# RPi_Clock_I2C.net
KiCad netlist of a schematic drawn in EAGLE
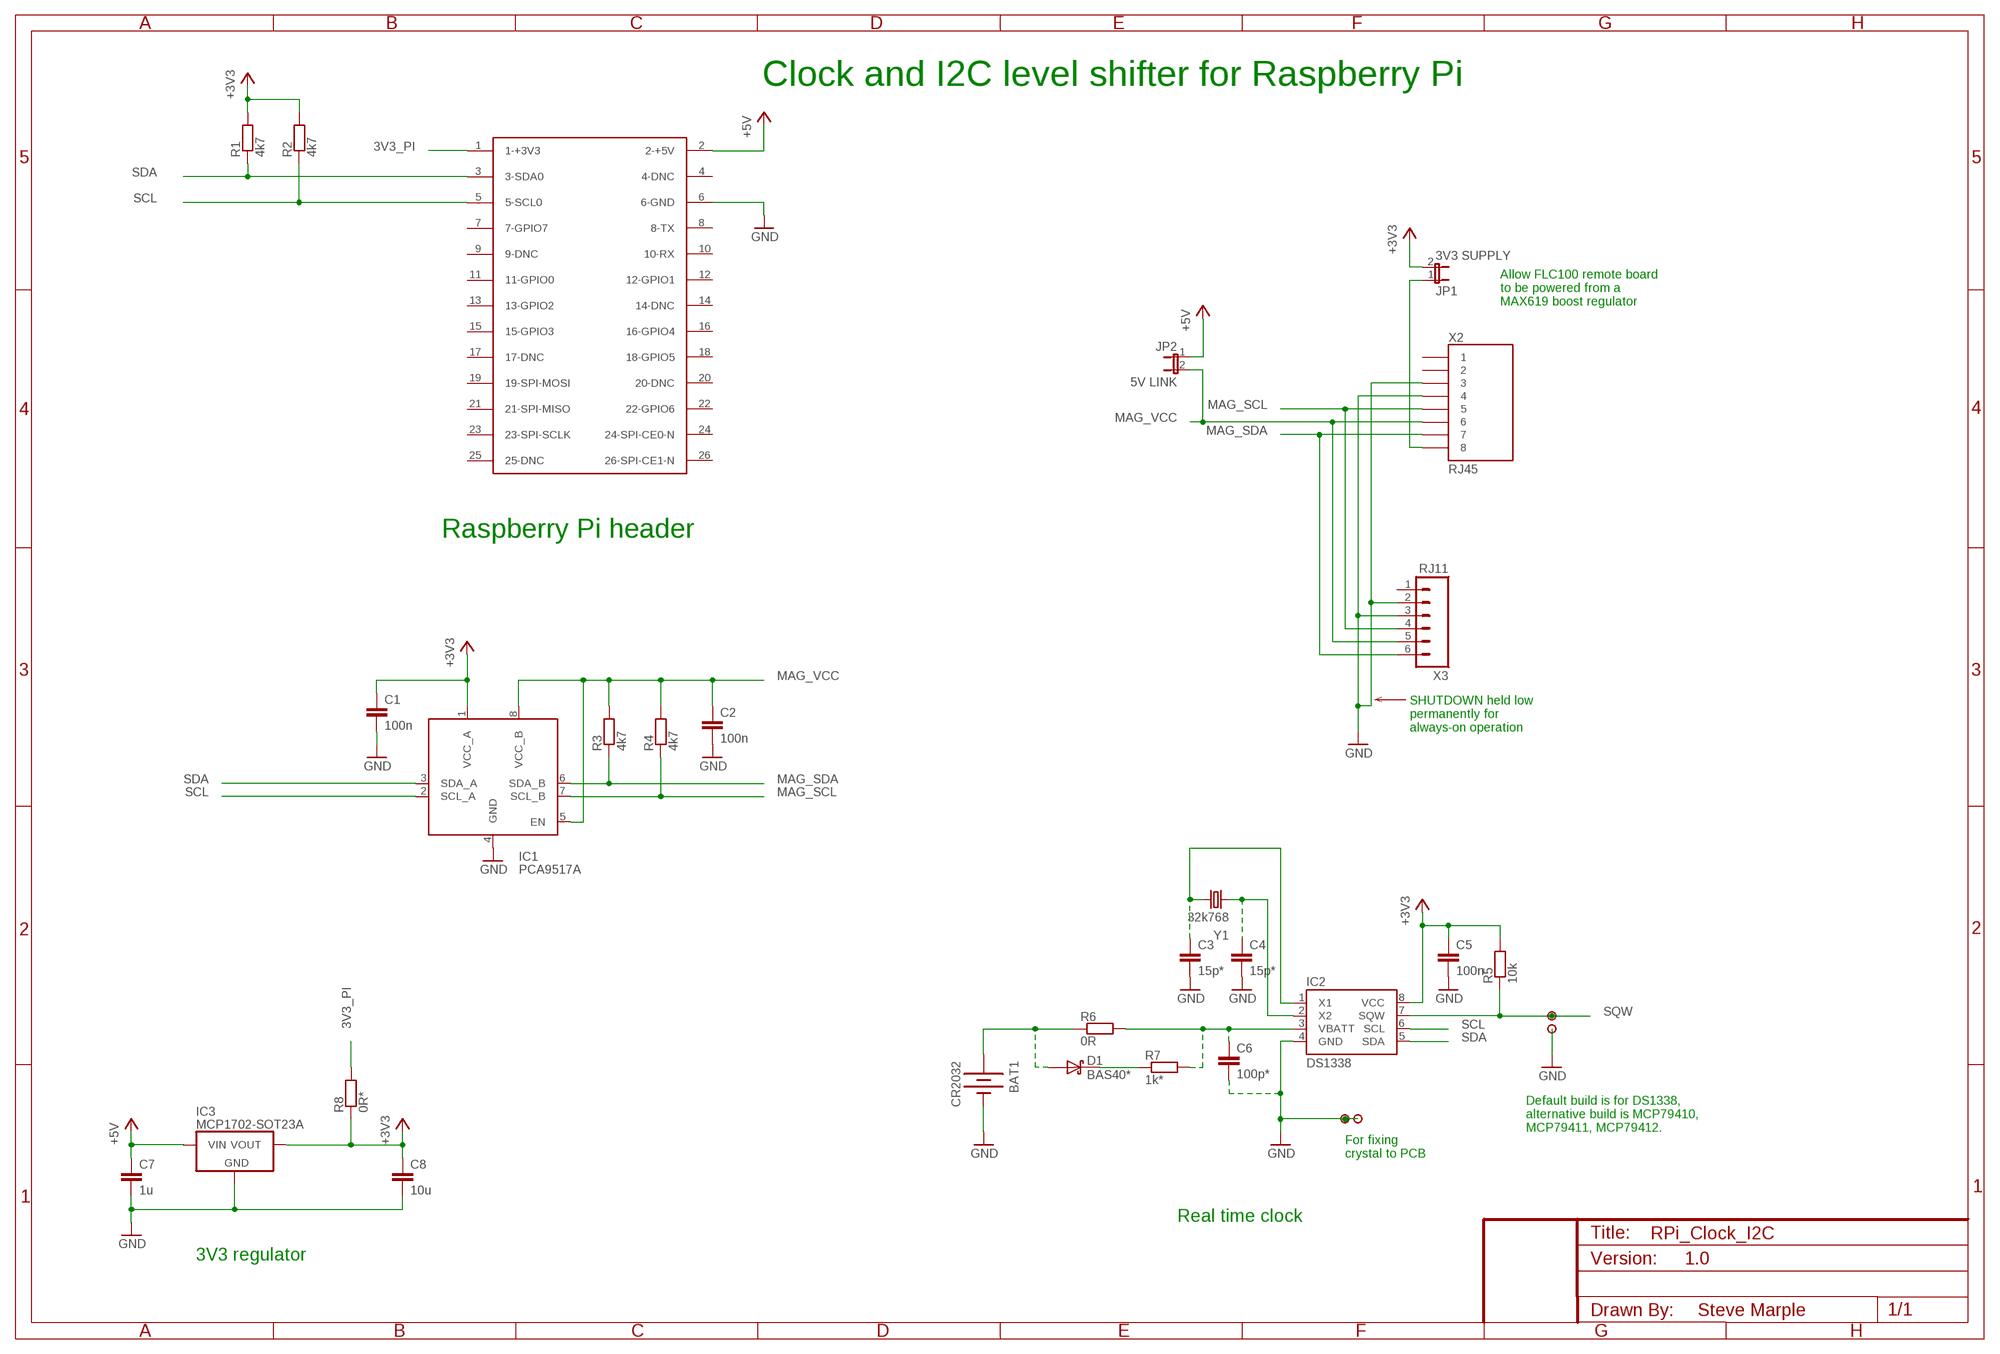
[diagram p0: schematic, sheet 1]

(export (version "E")
  (design (tool "Eeschema 10.0.6"))
  (components
    (comp (ref "BAT1")
      (value "CR2032")
      (footprint "eagle-import:BATTCOM_20MM_PTH")
      (libsource (lib "eagle-import") (part "BATTERY20PTH"))
    )
    (comp (ref "C1")
      (value "100n")
      (footprint "eagle-import:1206-HAND")
      (libsource (lib "eagle-import") (part "C-EU1206-HAND"))
    )
    (comp (ref "C2")
      (value "100n")
      (footprint "eagle-import:1206-HAND")
      (libsource (lib "eagle-import") (part "C-EU1206-HAND"))
    )
    (comp (ref "C3")
      (value "15p*")
      (footprint "eagle-import:0805-HAND")
      (libsource (lib "eagle-import") (part "C-EU0805-HAND"))
    )
    (comp (ref "C4")
      (value "15p*")
      (footprint "eagle-import:0805-HAND")
      (libsource (lib "eagle-import") (part "C-EU0805-HAND"))
    )
    (comp (ref "C5")
      (value "100n")
      (footprint "eagle-import:1206-HAND")
      (libsource (lib "eagle-import") (part "C-EU1206-HAND"))
    )
    (comp (ref "C6")
      (value "100p*")
      (footprint "eagle-import:1206-HAND")
      (libsource (lib "eagle-import") (part "C-EU1206-HAND"))
    )
    (comp (ref "C7")
      (value "1u")
      (footprint "eagle-import:1206-HAND")
      (libsource (lib "eagle-import") (part "C-EU1206-HAND"))
    )
    (comp (ref "C8")
      (value "10u")
      (footprint "eagle-import:1206-HAND")
      (libsource (lib "eagle-import") (part "C-EU1206-HAND"))
    )
    (comp (ref "D1")
      (value "BAS40*")
      (footprint "eagle-import:SOT23-3-HAND")
      (libsource (lib "eagle-import") (part "DIODE-SCHOTTKYSOT23-1-3-HAND"))
    )
    (comp (ref "IC1")
      (value "PCA9517A")
      (footprint "eagle-import:SO08")
      (libsource (lib "eagle-import") (part "PCA9517ASOIC"))
    )
    (comp (ref "IC2")
      (value "DS1338")
      (footprint "eagle-import:SO08")
      (libsource (lib "eagle-import") (part "DS1307SO08"))
    )
    (comp (ref "IC3")
      (value "MCP1702-SOT23A")
      (footprint "eagle-import:SOT23-3-HAND")
      (libsource (lib "eagle-import") (part "MCP1702SOT23-HAND"))
    )
    (comp (ref "JP1")
      (value "3V3 SUPPLY")
      (footprint "eagle-import:1X02")
      (libsource (lib "eagle-import") (part "JUMPER-2PTH"))
    )
    (comp (ref "JP2")
      (value "5V LINK")
      (footprint "eagle-import:1X02")
      (libsource (lib "eagle-import") (part "JUMPER-2PTH"))
    )
    (comp (ref "R1")
      (value "4k7")
      (footprint "eagle-import:1206-HAND")
      (libsource (lib "eagle-import") (part "RESISTOR1206-HAND"))
    )
    (comp (ref "R2")
      (value "4k7")
      (footprint "eagle-import:1206-HAND")
      (libsource (lib "eagle-import") (part "RESISTOR1206-HAND"))
    )
    (comp (ref "R3")
      (value "4k7")
      (footprint "eagle-import:1206-HAND")
      (libsource (lib "eagle-import") (part "RESISTOR1206-HAND"))
    )
    (comp (ref "R4")
      (value "4k7")
      (footprint "eagle-import:1206-HAND")
      (libsource (lib "eagle-import") (part "RESISTOR1206-HAND"))
    )
    (comp (ref "R5")
      (value "10k")
      (footprint "eagle-import:1206-HAND")
      (libsource (lib "eagle-import") (part "RESISTOR1206-HAND"))
    )
    (comp (ref "R6")
      (value "0R")
      (footprint "eagle-import:1206-HAND")
      (libsource (lib "eagle-import") (part "RESISTOR1206-HAND"))
    )
    (comp (ref "R7")
      (value "1k*")
      (footprint "eagle-import:1206-HAND")
      (libsource (lib "eagle-import") (part "RESISTOR1206-HAND"))
    )
    (comp (ref "R8")
      (value "0R*")
      (footprint "eagle-import:1206-HAND")
      (libsource (lib "eagle-import") (part "RESISTOR1206-HAND"))
    )
    (comp (ref "U$1")
      (value "PAD")
      (footprint "eagle-import:PAD")
      (libsource (lib "eagle-import") (part "PAD"))
    )
    (comp (ref "U$2")
      (value "PAD")
      (footprint "eagle-import:PAD")
      (libsource (lib "eagle-import") (part "PAD"))
    )
    (comp (ref "U$3")
      (value "PADSMALL")
      (footprint "eagle-import:PAD-SMALL")
      (libsource (lib "eagle-import") (part "PADSMALL"))
    )
    (comp (ref "U$4")
      (value "PADSMALL")
      (footprint "eagle-import:PAD-SMALL")
      (libsource (lib "eagle-import") (part "PADSMALL"))
    )
    (comp (ref "X1")
      (value "P1")
      (footprint "eagle-import:RASPBERRY-PI-HEADER")
      (libsource (lib "eagle-import") (part "RASPBERRY-PIHEADER"))
    )
    (comp (ref "X2")
      (value "RJ45")
      (footprint "eagle-import:RJ45-8")
      (libsource (lib "eagle-import") (part "RJ45-8PTH"))
    )
    (comp (ref "X3")
      (value "RJ11")
      (footprint "eagle-import:RJ11-6")
      (libsource (lib "eagle-import") (part "RJ11-6PTH"))
    )
    (comp (ref "Y1")
      (value "32k768")
      (footprint "eagle-import:TC38H")
      (libsource (lib "eagle-import") (part "CRYSTALTC38H"))
    )
  )
  (nets
    (net (code "1") (name "+3V3") (class "Default")
      (node (ref "C1") (pin "1") (pinfunction "1_1") (pintype "passive"))
      (node (ref "C5") (pin "1") (pinfunction "1_1") (pintype "passive"))
      (node (ref "C8") (pin "1") (pinfunction "1_1") (pintype "passive"))
      (node (ref "IC1") (pin "1") (pinfunction "VCC_A_1") (pintype "power_in"))
      (node (ref "IC2") (pin "8") (pinfunction "VCC_8") (pintype "bidirectional"))
      (node (ref "IC3") (pin "2") (pinfunction "VOUT_2") (pintype "passive"))
      (node (ref "JP1") (pin "2") (pinfunction "2_2") (pintype "passive"))
      (node (ref "R1") (pin "2") (pinfunction "2_2") (pintype "passive"))
      (node (ref "R2") (pin "2") (pinfunction "2_2") (pintype "passive"))
      (node (ref "R5") (pin "2") (pinfunction "2_2") (pintype "passive"))
      (node (ref "R8") (pin "1") (pinfunction "1_1") (pintype "passive"))
    )
    (net (code "2") (name "+5V") (class "Default")
      (node (ref "C7") (pin "1") (pinfunction "1_1") (pintype "passive"))
      (node (ref "IC3") (pin "3") (pinfunction "VIN_3") (pintype "input"))
      (node (ref "JP2") (pin "1") (pinfunction "1_1") (pintype "passive"))
      (node (ref "X1") (pin "2") (pinfunction "2-+5V_2") (pintype "bidirectional"))
    )
    (net (code "3") (name "/3V3_PI") (class "Default")
      (node (ref "R8") (pin "2") (pinfunction "2_2") (pintype "passive"))
      (node (ref "X1") (pin "1") (pinfunction "1-+3V3_1") (pintype "bidirectional"))
    )
    (net (code "4") (name "/MAG_SCL") (class "Default")
      (node (ref "IC1") (pin "7") (pinfunction "SCL_B_7") (pintype "bidirectional"))
      (node (ref "R4") (pin "1") (pinfunction "1_1") (pintype "passive"))
      (node (ref "X2") (pin "5") (pinfunction "5_5") (pintype "bidirectional"))
      (node (ref "X3") (pin "4") (pinfunction "4_4") (pintype "passive"))
    )
    (net (code "5") (name "/MAG_SDA") (class "Default")
      (node (ref "IC1") (pin "6") (pinfunction "SDA_B_6") (pintype "bidirectional"))
      (node (ref "R3") (pin "1") (pinfunction "1_1") (pintype "passive"))
      (node (ref "X2") (pin "7") (pinfunction "7_7") (pintype "bidirectional"))
      (node (ref "X3") (pin "6") (pinfunction "6_6") (pintype "passive"))
    )
    (net (code "6") (name "/MAG_VCC") (class "Default")
      (node (ref "C2") (pin "1") (pinfunction "1_1") (pintype "passive"))
      (node (ref "IC1") (pin "5") (pinfunction "EN_5") (pintype "bidirectional"))
      (node (ref "IC1") (pin "8") (pinfunction "VCC_B_8") (pintype "power_in"))
      (node (ref "JP2") (pin "2") (pinfunction "2_2") (pintype "passive"))
      (node (ref "R3") (pin "2") (pinfunction "2_2") (pintype "passive"))
      (node (ref "R4") (pin "2") (pinfunction "2_2") (pintype "passive"))
      (node (ref "X2") (pin "6") (pinfunction "6_6") (pintype "bidirectional"))
      (node (ref "X3") (pin "5") (pinfunction "5_5") (pintype "passive"))
    )
    (net (code "7") (name "/SCL") (class "Default")
      (node (ref "IC1") (pin "2") (pinfunction "SCL_A_2") (pintype "bidirectional"))
      (node (ref "IC2") (pin "6") (pinfunction "SCL_6") (pintype "bidirectional"))
      (node (ref "R2") (pin "1") (pinfunction "1_1") (pintype "passive"))
      (node (ref "X1") (pin "5") (pinfunction "5-SCL0_5") (pintype "bidirectional"))
    )
    (net (code "8") (name "/SDA") (class "Default")
      (node (ref "IC1") (pin "3") (pinfunction "SDA_A_3") (pintype "bidirectional"))
      (node (ref "IC2") (pin "5") (pinfunction "SDA_5") (pintype "bidirectional"))
      (node (ref "R1") (pin "1") (pinfunction "1_1") (pintype "passive"))
      (node (ref "X1") (pin "3") (pinfunction "3-SDA0_3") (pintype "bidirectional"))
    )
    (net (code "9") (name "/SQW") (class "Default")
      (node (ref "IC2") (pin "7") (pinfunction "SQW_7") (pintype "bidirectional"))
      (node (ref "R5") (pin "1") (pinfunction "1_1") (pintype "passive"))
      (node (ref "U$1") (pin "1") (pinfunction "1_1") (pintype "bidirectional"))
    )
    (net (code "10") (name "GND") (class "Default")
      (node (ref "BAT1") (pin "2") (pinfunction "-_2") (pintype "power_in"))
      (node (ref "C1") (pin "2") (pinfunction "2_2") (pintype "passive"))
      (node (ref "C2") (pin "2") (pinfunction "2_2") (pintype "passive"))
      (node (ref "C3") (pin "2") (pinfunction "2_2") (pintype "passive"))
      (node (ref "C4") (pin "2") (pinfunction "2_2") (pintype "passive"))
      (node (ref "C5") (pin "2") (pinfunction "2_2") (pintype "passive"))
      (node (ref "C6") (pin "2") (pinfunction "2_2") (pintype "passive"))
      (node (ref "C7") (pin "2") (pinfunction "2_2") (pintype "passive"))
      (node (ref "C8") (pin "2") (pinfunction "2_2") (pintype "passive"))
      (node (ref "IC1") (pin "4") (pinfunction "GND_4") (pintype "power_in"))
      (node (ref "IC2") (pin "4") (pinfunction "GND_4") (pintype "bidirectional"))
      (node (ref "IC3") (pin "1") (pinfunction "GND_1") (pintype "passive"))
      (node (ref "U$2") (pin "1") (pinfunction "1_1") (pintype "bidirectional"))
      (node (ref "U$3") (pin "1") (pinfunction "1_1") (pintype "bidirectional"))
      (node (ref "U$4") (pin "1") (pinfunction "1_1") (pintype "bidirectional"))
      (node (ref "X1") (pin "6") (pinfunction "6-GND_6") (pintype "bidirectional"))
      (node (ref "X2") (pin "3") (pinfunction "3_3") (pintype "bidirectional"))
      (node (ref "X2") (pin "4") (pinfunction "4_4") (pintype "bidirectional"))
      (node (ref "X3") (pin "2") (pinfunction "2_2") (pintype "passive"))
      (node (ref "X3") (pin "3") (pinfunction "3_3") (pintype "passive"))
    )
    (net (code "11") (name "Net-(BAT1-+)") (class "Default")
      (node (ref "BAT1") (pin "1") (pinfunction "+_1") (pintype "power_in"))
      (node (ref "D1") (pin "1") (pinfunction "A_1") (pintype "passive"))
      (node (ref "R6") (pin "1") (pinfunction "1_1") (pintype "passive"))
    )
    (net (code "12") (name "Net-(D1-C)") (class "Default")
      (node (ref "D1") (pin "3") (pinfunction "C_3") (pintype "passive"))
      (node (ref "R7") (pin "1") (pinfunction "1_1") (pintype "passive"))
    )
    (net (code "13") (name "Net-(IC2-VBATT)") (class "Default")
      (node (ref "C6") (pin "1") (pinfunction "1_1") (pintype "passive"))
      (node (ref "IC2") (pin "3") (pinfunction "VBATT_3") (pintype "bidirectional"))
      (node (ref "R6") (pin "2") (pinfunction "2_2") (pintype "passive"))
      (node (ref "R7") (pin "2") (pinfunction "2_2") (pintype "passive"))
    )
    (net (code "14") (name "Net-(IC2-X1)") (class "Default")
      (node (ref "C3") (pin "1") (pinfunction "1_1") (pintype "passive"))
      (node (ref "IC2") (pin "1") (pinfunction "X1_1") (pintype "bidirectional"))
      (node (ref "Y1") (pin "1") (pinfunction "1_1") (pintype "passive"))
    )
    (net (code "15") (name "Net-(IC2-X2)") (class "Default")
      (node (ref "C4") (pin "1") (pinfunction "1_1") (pintype "passive"))
      (node (ref "IC2") (pin "2") (pinfunction "X2_2") (pintype "bidirectional"))
      (node (ref "Y1") (pin "2") (pinfunction "2_2") (pintype "passive"))
    )
    (net (code "16") (name "Net-(JP1-Pad1)") (class "Default")
      (node (ref "JP1") (pin "1") (pinfunction "1_1") (pintype "passive"))
      (node (ref "X2") (pin "8") (pinfunction "8_8") (pintype "bidirectional"))
    )
    (net (code "17") (name "unconnected-(X1-4-DNC-Pad4)") (class "Default")
      (node (ref "X1") (pin "4") (pinfunction "4-DNC_4") (pintype "bidirectional"))
    )
    (net (code "18") (name "unconnected-(X1-7-GPIO7-Pad7)") (class "Default")
      (node (ref "X1") (pin "7") (pinfunction "7-GPIO7_7") (pintype "bidirectional"))
    )
    (net (code "19") (name "unconnected-(X1-8-TX-Pad8)") (class "Default")
      (node (ref "X1") (pin "8") (pinfunction "8-TX_8") (pintype "bidirectional"))
    )
    (net (code "20") (name "unconnected-(X1-9-DNC-Pad9)") (class "Default")
      (node (ref "X1") (pin "9") (pinfunction "9-DNC_9") (pintype "bidirectional"))
    )
    (net (code "21") (name "unconnected-(X1-10-RX-Pad10)") (class "Default")
      (node (ref "X1") (pin "10") (pinfunction "10-RX_10") (pintype "bidirectional"))
    )
    (net (code "22") (name "unconnected-(X1-11-GPIO0-Pad11)") (class "Default")
      (node (ref "X1") (pin "11") (pinfunction "11-GPIO0_11") (pintype "bidirectional"))
    )
    (net (code "23") (name "unconnected-(X1-12-GPIO1-Pad12)") (class "Default")
      (node (ref "X1") (pin "12") (pinfunction "12-GPIO1_12") (pintype "bidirectional"))
    )
    (net (code "24") (name "unconnected-(X1-13-GPIO2-Pad13)") (class "Default")
      (node (ref "X1") (pin "13") (pinfunction "13-GPIO2_13") (pintype "bidirectional"))
    )
    (net (code "25") (name "unconnected-(X1-14-DNC-Pad14)") (class "Default")
      (node (ref "X1") (pin "14") (pinfunction "14-DNC_14") (pintype "bidirectional"))
    )
    (net (code "26") (name "unconnected-(X1-15-GPIO3-Pad15)") (class "Default")
      (node (ref "X1") (pin "15") (pinfunction "15-GPIO3_15") (pintype "bidirectional"))
    )
    (net (code "27") (name "unconnected-(X1-16-GPIO4-Pad16)") (class "Default")
      (node (ref "X1") (pin "16") (pinfunction "16-GPIO4_16") (pintype "bidirectional"))
    )
    (net (code "28") (name "unconnected-(X1-17-DNC-Pad17)") (class "Default")
      (node (ref "X1") (pin "17") (pinfunction "17-DNC_17") (pintype "bidirectional"))
    )
    (net (code "29") (name "unconnected-(X1-18-GPIO5-Pad18)") (class "Default")
      (node (ref "X1") (pin "18") (pinfunction "18-GPIO5_18") (pintype "bidirectional"))
    )
    (net (code "30") (name "unconnected-(X1-19-SPI-MOSI-Pad19)") (class "Default")
      (node (ref "X1") (pin "19") (pinfunction "19-SPI-MOSI_19") (pintype "bidirectional"))
    )
    (net (code "31") (name "unconnected-(X1-20-DNC-Pad20)") (class "Default")
      (node (ref "X1") (pin "20") (pinfunction "20-DNC_20") (pintype "bidirectional"))
    )
    (net (code "32") (name "unconnected-(X1-21-SPI-MISO-Pad21)") (class "Default")
      (node (ref "X1") (pin "21") (pinfunction "21-SPI-MISO_21") (pintype "bidirectional"))
    )
    (net (code "33") (name "unconnected-(X1-22-GPIO6-Pad22)") (class "Default")
      (node (ref "X1") (pin "22") (pinfunction "22-GPIO6_22") (pintype "bidirectional"))
    )
    (net (code "34") (name "unconnected-(X1-23-SPI-SCLK-Pad23)") (class "Default")
      (node (ref "X1") (pin "23") (pinfunction "23-SPI-SCLK_23") (pintype "bidirectional"))
    )
    (net (code "35") (name "unconnected-(X1-24-SPI-CE0-N-Pad24)") (class "Default")
      (node (ref "X1") (pin "24") (pinfunction "24-SPI-CE0-N_24") (pintype "bidirectional"))
    )
    (net (code "36") (name "unconnected-(X1-25-DNC-Pad25)") (class "Default")
      (node (ref "X1") (pin "25") (pinfunction "25-DNC_25") (pintype "bidirectional"))
    )
    (net (code "37") (name "unconnected-(X1-26-SPI-CE1-N-Pad26)") (class "Default")
      (node (ref "X1") (pin "26") (pinfunction "26-SPI-CE1-N_26") (pintype "bidirectional"))
    )
    (net (code "38") (name "unconnected-(X2-Pad1)") (class "Default")
      (node (ref "X2") (pin "1") (pinfunction "1_1") (pintype "bidirectional"))
    )
    (net (code "39") (name "unconnected-(X2-Pad2)") (class "Default")
      (node (ref "X2") (pin "2") (pinfunction "2_2") (pintype "bidirectional"))
    )
    (net (code "40") (name "unconnected-(X3-Pad1)") (class "Default")
      (node (ref "X3") (pin "1") (pinfunction "1_1") (pintype "passive"))
    )
  )
)
